# 03_AI_PFI_Connector.net
KiCad netlist of a schematic drawn in Altium Designer
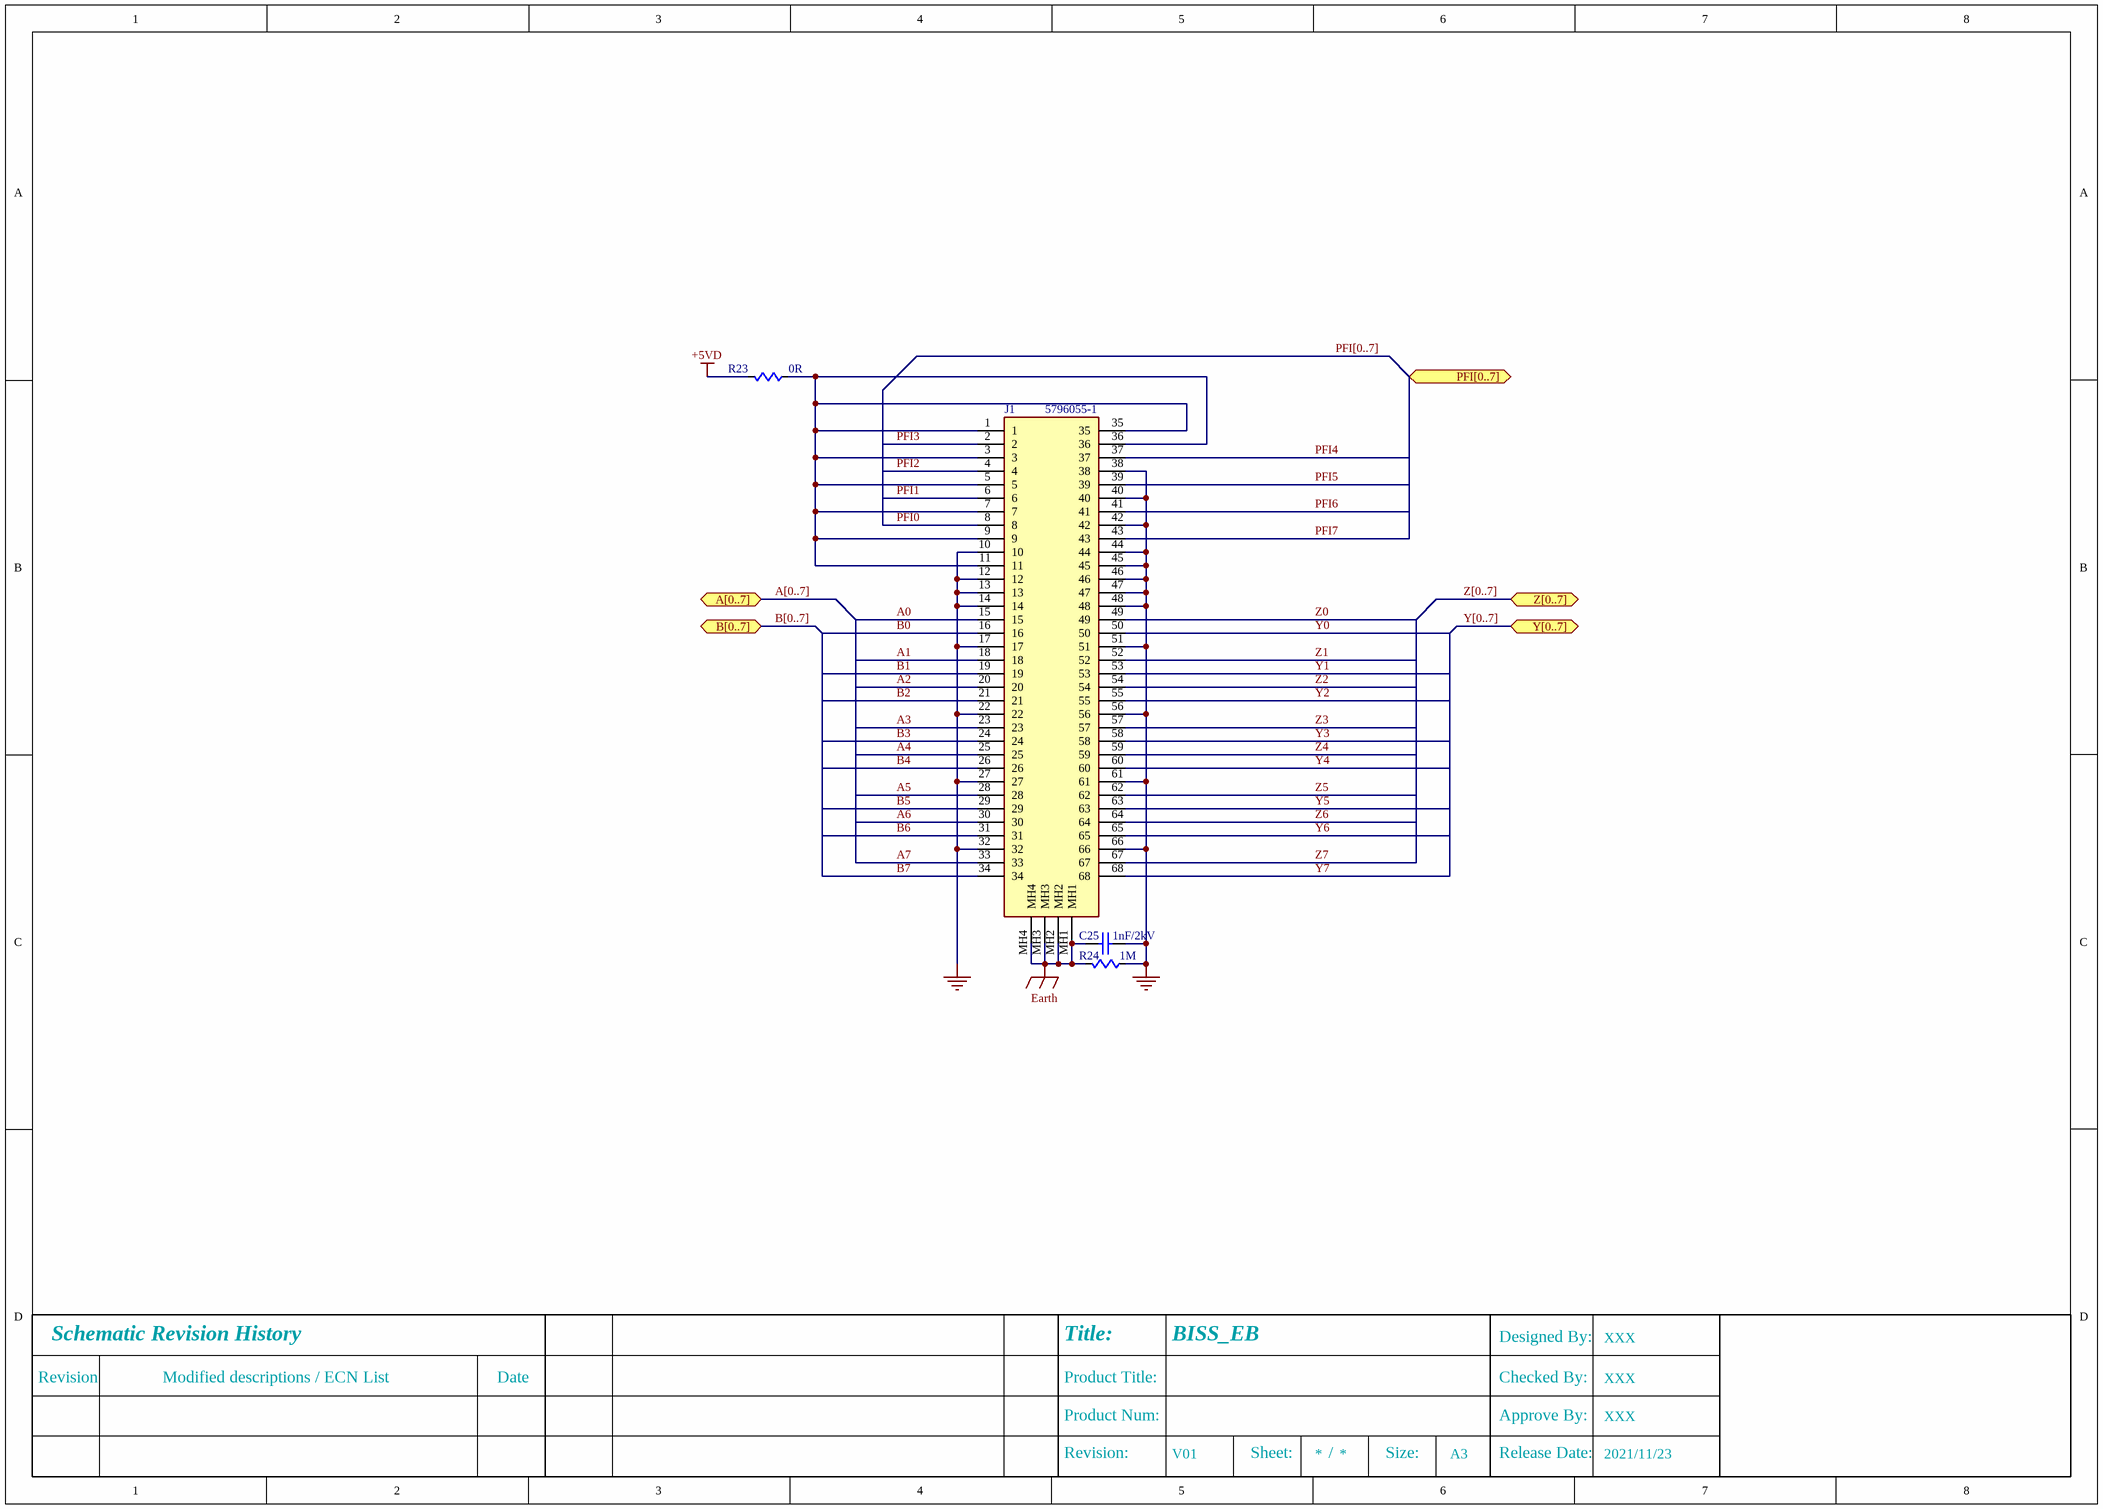
[diagram p0: 03_AI_PFI_Connector.SchDoc]

(export (version "E")
  (design (tool "Eeschema 10.0.6"))
  (components
    (comp (ref "C25")
      (value "1nF/2kV")
      (footprint "SamacSys:C1206")
      (description "MLCC")
      (libsource (lib "SamacSys") (part "C"))
    )
    (comp (ref "J1")
      (value "5796055-1")
      (footprint "SamacSys:57960551")
      (description "Connector")
      (fields (field (name "MOUSER PART NUMBER") "571-5796055-1"))
      (libsource (lib "SamacSys") (part "5796055-1"))
    )
    (comp (ref "R23")
      (value "0R")
      (footprint "SamacSys:R0805")
      (description "贴片电阻")
      (libsource (lib "SamacSys") (part "R"))
    )
    (comp (ref "R24")
      (value "1M")
      (footprint "SamacSys:R1206")
      (description "贴片电阻 1206")
      (libsource (lib "SamacSys") (part "R"))
    )
  )
  (nets
    (net (code "1") (name "+5VD") (class "Default")
      (node (ref "R23") (pin "2") (pinfunction "2_2") (pintype "passive"))
    )
    (net (code "2") (name "/A0") (class "Default")
      (node (ref "J1") (pin "15") (pinfunction "15_15") (pintype "passive"))
    )
    (net (code "3") (name "/A1") (class "Default")
      (node (ref "J1") (pin "18") (pinfunction "18_18") (pintype "passive"))
    )
    (net (code "4") (name "/A2") (class "Default")
      (node (ref "J1") (pin "20") (pinfunction "20_20") (pintype "passive"))
    )
    (net (code "5") (name "/A3") (class "Default")
      (node (ref "J1") (pin "23") (pinfunction "23_23") (pintype "passive"))
    )
    (net (code "6") (name "/A4") (class "Default")
      (node (ref "J1") (pin "25") (pinfunction "25_25") (pintype "passive"))
    )
    (net (code "7") (name "/A5") (class "Default")
      (node (ref "J1") (pin "28") (pinfunction "28_28") (pintype "passive"))
    )
    (net (code "8") (name "/A6") (class "Default")
      (node (ref "J1") (pin "30") (pinfunction "30_30") (pintype "passive"))
    )
    (net (code "9") (name "/A7") (class "Default")
      (node (ref "J1") (pin "33") (pinfunction "33_33") (pintype "passive"))
    )
    (net (code "11") (name "/B0") (class "Default")
      (node (ref "J1") (pin "16") (pinfunction "16_16") (pintype "passive"))
    )
    (net (code "12") (name "/B1") (class "Default")
      (node (ref "J1") (pin "19") (pinfunction "19_19") (pintype "passive"))
    )
    (net (code "13") (name "/B2") (class "Default")
      (node (ref "J1") (pin "21") (pinfunction "21_21") (pintype "passive"))
    )
    (net (code "14") (name "/B3") (class "Default")
      (node (ref "J1") (pin "24") (pinfunction "24_24") (pintype "passive"))
    )
    (net (code "15") (name "/B4") (class "Default")
      (node (ref "J1") (pin "26") (pinfunction "26_26") (pintype "passive"))
    )
    (net (code "16") (name "/B5") (class "Default")
      (node (ref "J1") (pin "29") (pinfunction "29_29") (pintype "passive"))
    )
    (net (code "17") (name "/B6") (class "Default")
      (node (ref "J1") (pin "31") (pinfunction "31_31") (pintype "passive"))
    )
    (net (code "18") (name "/B7") (class "Default")
      (node (ref "J1") (pin "34") (pinfunction "34_34") (pintype "passive"))
    )
    (net (code "20") (name "/PFI0") (class "Default")
      (node (ref "J1") (pin "8") (pinfunction "8_8") (pintype "passive"))
    )
    (net (code "21") (name "/PFI1") (class "Default")
      (node (ref "J1") (pin "6") (pinfunction "6_6") (pintype "passive"))
    )
    (net (code "22") (name "/PFI2") (class "Default")
      (node (ref "J1") (pin "4") (pinfunction "4_4") (pintype "passive"))
    )
    (net (code "23") (name "/PFI3") (class "Default")
      (node (ref "J1") (pin "2") (pinfunction "2_2") (pintype "passive"))
    )
    (net (code "24") (name "/PFI4") (class "Default")
      (node (ref "J1") (pin "37") (pinfunction "37_37") (pintype "passive"))
    )
    (net (code "25") (name "/PFI5") (class "Default")
      (node (ref "J1") (pin "39") (pinfunction "39_39") (pintype "passive"))
    )
    (net (code "26") (name "/PFI6") (class "Default")
      (node (ref "J1") (pin "41") (pinfunction "41_41") (pintype "passive"))
    )
    (net (code "27") (name "/PFI7") (class "Default")
      (node (ref "J1") (pin "43") (pinfunction "43_43") (pintype "passive"))
    )
    (net (code "29") (name "/Y0") (class "Default")
      (node (ref "J1") (pin "50") (pinfunction "50_50") (pintype "passive"))
    )
    (net (code "30") (name "/Y1") (class "Default")
      (node (ref "J1") (pin "53") (pinfunction "53_53") (pintype "passive"))
    )
    (net (code "31") (name "/Y2") (class "Default")
      (node (ref "J1") (pin "55") (pinfunction "55_55") (pintype "passive"))
    )
    (net (code "32") (name "/Y3") (class "Default")
      (node (ref "J1") (pin "58") (pinfunction "58_58") (pintype "passive"))
    )
    (net (code "33") (name "/Y4") (class "Default")
      (node (ref "J1") (pin "60") (pinfunction "60_60") (pintype "passive"))
    )
    (net (code "34") (name "/Y5") (class "Default")
      (node (ref "J1") (pin "63") (pinfunction "63_63") (pintype "passive"))
    )
    (net (code "35") (name "/Y6") (class "Default")
      (node (ref "J1") (pin "65") (pinfunction "65_65") (pintype "passive"))
    )
    (net (code "36") (name "/Y7") (class "Default")
      (node (ref "J1") (pin "68") (pinfunction "68_68") (pintype "passive"))
    )
    (net (code "38") (name "/Z0") (class "Default")
      (node (ref "J1") (pin "49") (pinfunction "49_49") (pintype "passive"))
    )
    (net (code "39") (name "/Z1") (class "Default")
      (node (ref "J1") (pin "52") (pinfunction "52_52") (pintype "passive"))
    )
    (net (code "40") (name "/Z2") (class "Default")
      (node (ref "J1") (pin "54") (pinfunction "54_54") (pintype "passive"))
    )
    (net (code "41") (name "/Z3") (class "Default")
      (node (ref "J1") (pin "57") (pinfunction "57_57") (pintype "passive"))
    )
    (net (code "42") (name "/Z4") (class "Default")
      (node (ref "J1") (pin "59") (pinfunction "59_59") (pintype "passive"))
    )
    (net (code "43") (name "/Z5") (class "Default")
      (node (ref "J1") (pin "62") (pinfunction "62_62") (pintype "passive"))
    )
    (net (code "44") (name "/Z6") (class "Default")
      (node (ref "J1") (pin "64") (pinfunction "64_64") (pintype "passive"))
    )
    (net (code "45") (name "/Z7") (class "Default")
      (node (ref "J1") (pin "67") (pinfunction "67_67") (pintype "passive"))
    )
    (net (code "47") (name "Earth") (class "Default")
      (node (ref "C25") (pin "1") (pinfunction "1_1") (pintype "passive"))
      (node (ref "J1") (pin "MH1") (pinfunction "MH1_MH1") (pintype "passive"))
      (node (ref "J1") (pin "MH2") (pinfunction "MH2_MH2") (pintype "passive"))
      (node (ref "J1") (pin "MH3") (pinfunction "MH3_MH3") (pintype "passive"))
      (node (ref "J1") (pin "MH4") (pinfunction "MH4_MH4") (pintype "passive"))
      (node (ref "R24") (pin "1") (pinfunction "1_1") (pintype "passive"))
    )
    (net (code "48") (name "GND") (class "Default")
      (node (ref "C25") (pin "2") (pinfunction "2_2") (pintype "passive"))
      (node (ref "J1") (pin "10") (pinfunction "10_10") (pintype "passive"))
      (node (ref "J1") (pin "12") (pinfunction "12_12") (pintype "passive"))
      (node (ref "J1") (pin "13") (pinfunction "13_13") (pintype "passive"))
      (node (ref "J1") (pin "14") (pinfunction "14_14") (pintype "passive"))
      (node (ref "J1") (pin "17") (pinfunction "17_17") (pintype "passive"))
      (node (ref "J1") (pin "22") (pinfunction "22_22") (pintype "passive"))
      (node (ref "J1") (pin "27") (pinfunction "27_27") (pintype "passive"))
      (node (ref "J1") (pin "32") (pinfunction "32_32") (pintype "passive"))
      (node (ref "J1") (pin "38") (pinfunction "38_38") (pintype "passive"))
      (node (ref "J1") (pin "40") (pinfunction "40_40") (pintype "passive"))
      (node (ref "J1") (pin "42") (pinfunction "42_42") (pintype "passive"))
      (node (ref "J1") (pin "44") (pinfunction "44_44") (pintype "passive"))
      (node (ref "J1") (pin "45") (pinfunction "45_45") (pintype "passive"))
      (node (ref "J1") (pin "46") (pinfunction "46_46") (pintype "passive"))
      (node (ref "J1") (pin "47") (pinfunction "47_47") (pintype "passive"))
      (node (ref "J1") (pin "48") (pinfunction "48_48") (pintype "passive"))
      (node (ref "J1") (pin "51") (pinfunction "51_51") (pintype "passive"))
      (node (ref "J1") (pin "56") (pinfunction "56_56") (pintype "passive"))
      (node (ref "J1") (pin "61") (pinfunction "61_61") (pintype "passive"))
      (node (ref "J1") (pin "66") (pinfunction "66_66") (pintype "passive"))
      (node (ref "R24") (pin "2") (pinfunction "2_2") (pintype "passive"))
    )
    (net (code "49") (name "Net-(J1-Pad1)") (class "Default")
      (node (ref "J1") (pin "1") (pinfunction "1_1") (pintype "passive"))
      (node (ref "J1") (pin "11") (pinfunction "11_11") (pintype "passive"))
      (node (ref "J1") (pin "3") (pinfunction "3_3") (pintype "passive"))
      (node (ref "J1") (pin "35") (pinfunction "35_35") (pintype "passive"))
      (node (ref "J1") (pin "36") (pinfunction "36_36") (pintype "passive"))
      (node (ref "J1") (pin "5") (pinfunction "5_5") (pintype "passive"))
      (node (ref "J1") (pin "7") (pinfunction "7_7") (pintype "passive"))
      (node (ref "J1") (pin "9") (pinfunction "9_9") (pintype "passive"))
      (node (ref "R23") (pin "1") (pinfunction "1_1") (pintype "passive"))
    )
  )
)
